# STM32F103ZET6.net
KiCad netlist of a schematic drawn in Altium Designer
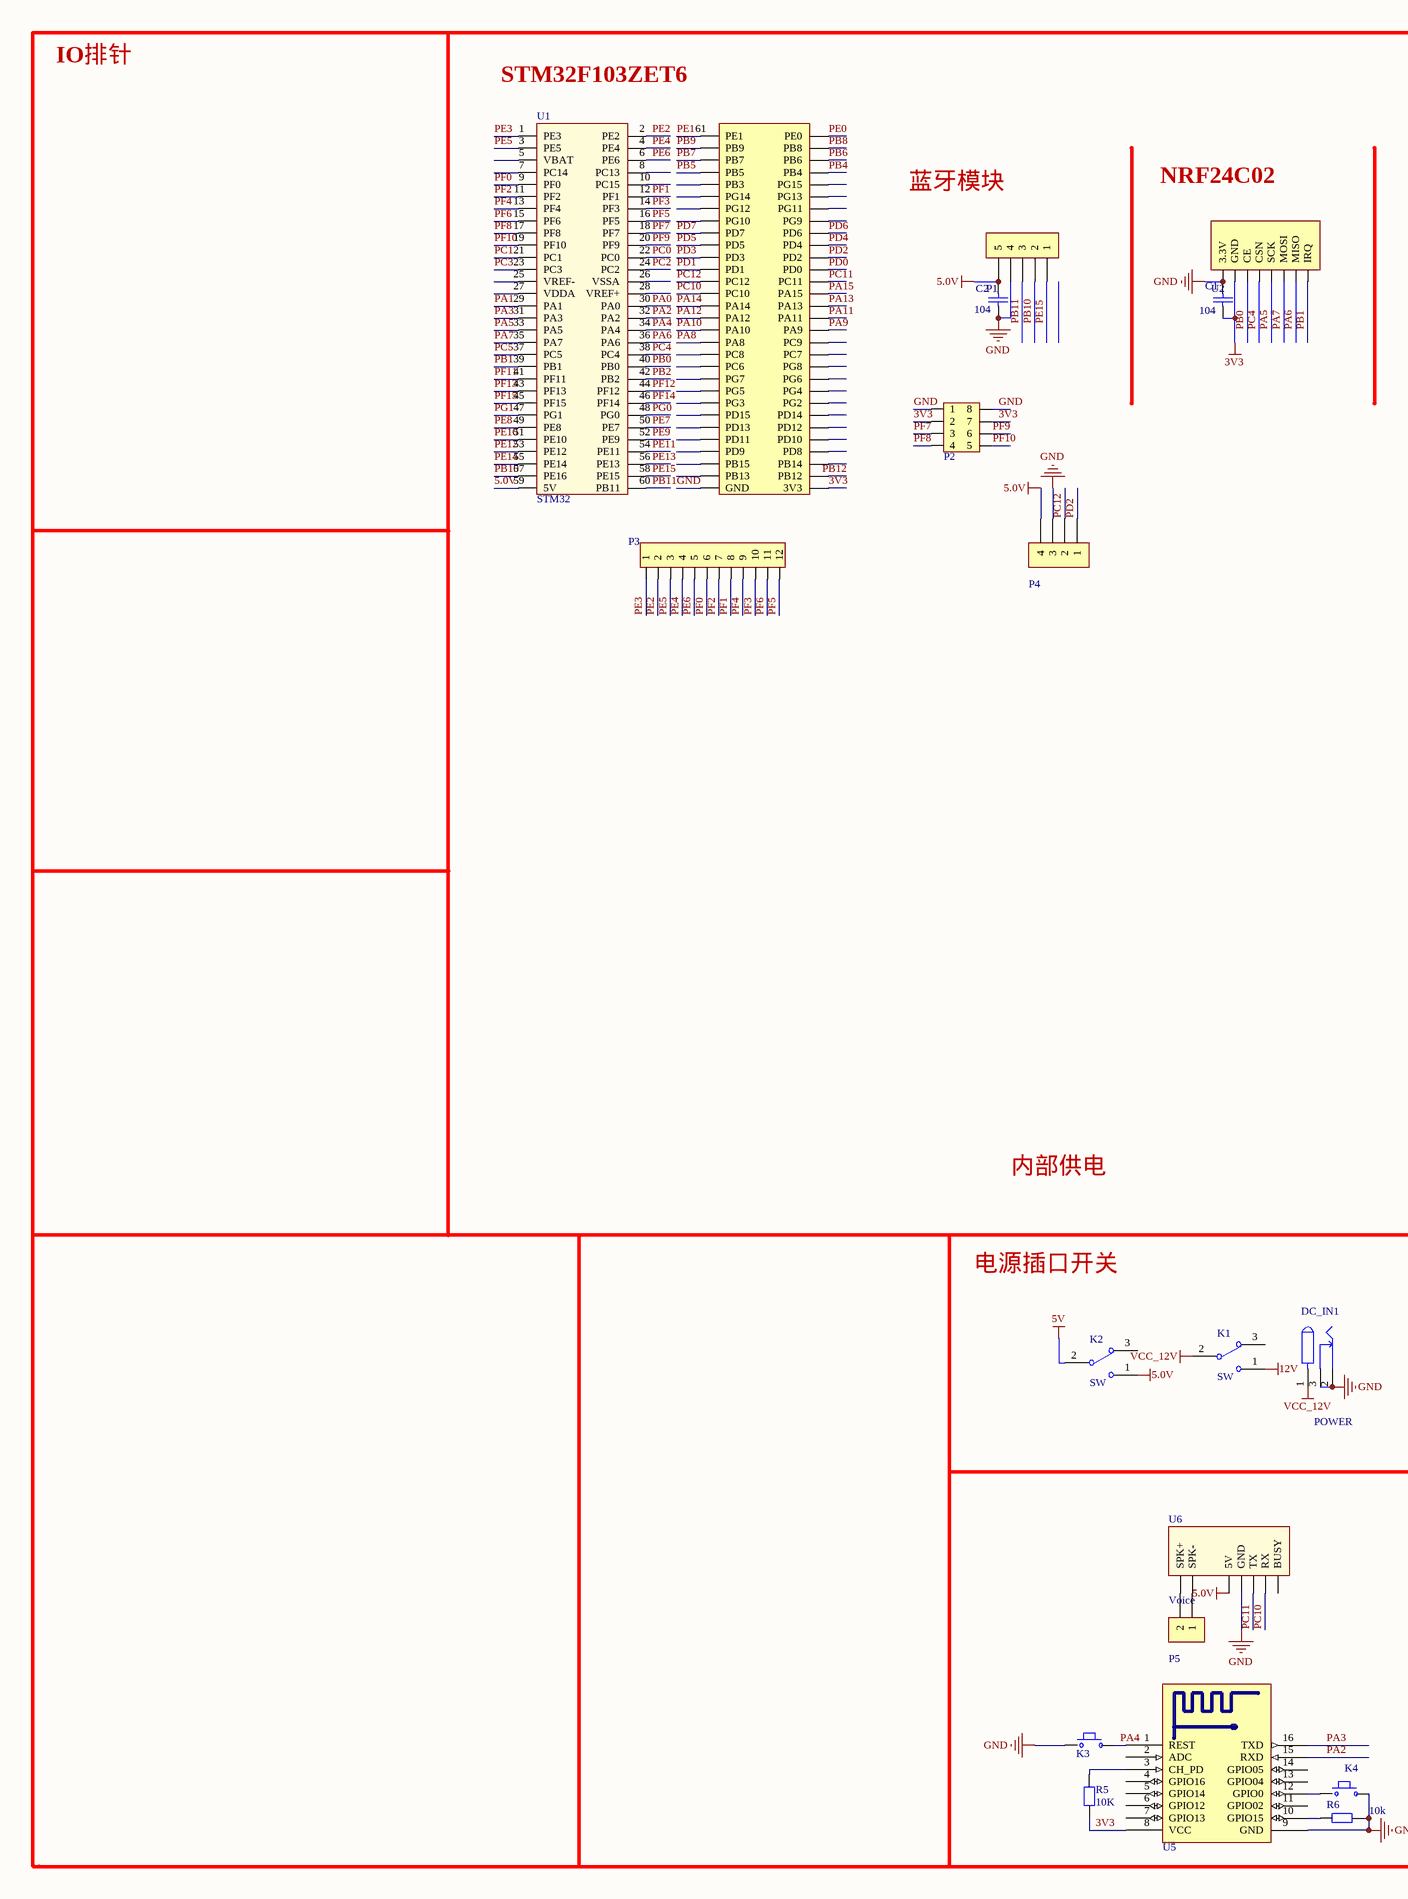
[diagram p0: 原子战舰STM32F103ZET6.SchDoc, left]
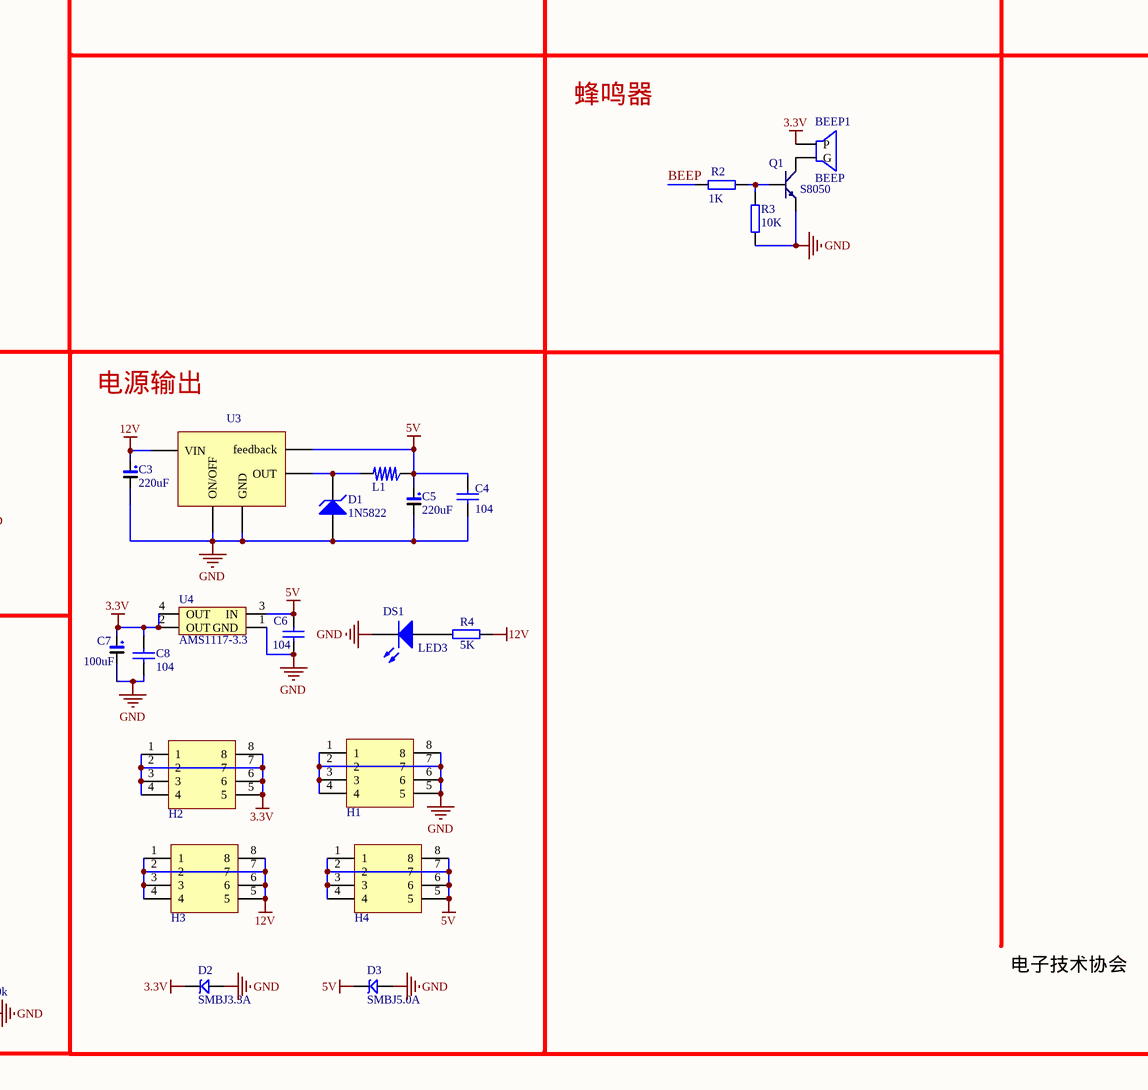
[diagram p1: 原子战舰STM32F103ZET6.SchDoc, right]

(export (version "E")
  (design (tool "Eeschema 10.0.6"))
  (components
    (comp (ref "BEEP1")
      (value "BEEP")
      (footprint "BELL-5")
      (libsource (lib "WarShip V3 STM32103封装库") (part "BEEP"))
    )
    (comp (ref "C1") (value "104") (footprint "C0805") (libsource (lib "周杏发的PCB库") (part "CAP0805")))
    (comp (ref "C2") (value "104") (footprint "C0805") (libsource (lib "周杏发的PCB库") (part "CAP0805")))
    (comp (ref "C3") (value "220uF") (footprint "CAP-470-16V") (libsource (lib "集成库") (part "CAP-470-16V")))
    (comp (ref "C4") (value "104") (footprint "C0805") (libsource (lib "周杏发的PCB库") (part "CAP0805")))
    (comp (ref "C5") (value "220uF") (footprint "CAP-470-16V") (libsource (lib "集成库") (part "CAP-470-16V")))
    (comp (ref "C6") (value "104") (footprint "C0805") (libsource (lib "周杏发的PCB库") (part "CAP0805")))
    (comp (ref "C7") (value "100uF") (footprint "CAP-470-16V") (libsource (lib "集成库") (part "CAP-470-16V")))
    (comp (ref "C8") (value "104") (footprint "C0805") (libsource (lib "周杏发的PCB库") (part "CAP0805")))
    (comp (ref "D1")
      (value "1N5822")
      (footprint "D-9.9X6.0MM")
      (description "Zener Diode")
      (libsource (lib "Miscellaneous Devices") (part "D Zener"))
    )
    (comp (ref "D2")
      (value "SMBJ3.3A")
      (footprint "SMBJ")
      (description "TVS")
      (libsource (lib "WarShip V3 STM32103封装库") (part "SMBJ"))
    )
    (comp (ref "D3")
      (value "SMBJ5.0A")
      (footprint "SMBJ")
      (description "TVS")
      (libsource (lib "WarShip V3 STM32103封装库") (part "SMBJ"))
    )
    (comp (ref "DC_IN1")
      (value "POWER")
      (footprint "DC10B")
      (libsource (lib "WarShip V3 STM32103封装库") (part "POW"))
    )
    (comp (ref "DS1")
      (value "LED3")
      (footprint "SMDLED")
      (description "Typical RED, GREEN, YELLOW, AMBER GaAs LED")
      (fields (field (name "PUBLISHER") "Altium Limited"))
      (libsource (lib "WarShip V3 STM32103封装库") (part "LED2"))
    )
    (comp (ref "H1")
      (value "Header2-4")
      (footprint "Header2-4")
      (libsource (lib "直插原理图库") (part "Header2-4"))
    )
    (comp (ref "H2")
      (value "Header2-4")
      (footprint "Header2-4")
      (libsource (lib "直插原理图库") (part "Header2-4"))
    )
    (comp (ref "H3")
      (value "Header2-4")
      (footprint "Header2-4")
      (libsource (lib "直插原理图库") (part "Header2-4"))
    )
    (comp (ref "H4")
      (value "Header2-4")
      (footprint "Header2-4")
      (libsource (lib "直插原理图库") (part "Header2-4"))
    )
    (comp (ref "K1") (value "SW") (footprint "SW-07") (libsource (lib "PCB_Project1") (part "SW-07")))
    (comp (ref "K2") (value "SW") (footprint "SW-07") (libsource (lib "PCB_Project1") (part "SW-07")))
    (comp (ref "K3") (value "SW-TP") (footprint "SW-TP") (libsource (lib "集成库") (part "SW-TP")))
    (comp (ref "K4") (value "SW-TP") (footprint "SW-TP") (libsource (lib "集成库") (part "SW-TP")))
    (comp (ref "L1")
      (value "4.7uH")
      (footprint "L_SOP74")
      (libsource (lib "WarShip V3 STM32103封装库") (part "L_SOP"))
    )
    (comp (ref "P1") (value "Header5") (footprint "Header5") (libsource (lib "集成库") (part "Header5")))
    (comp (ref "P2") (value "Header4X2") (footprint "Header4X2") (libsource (lib "集成库") (part "Header4X2")))
    (comp (ref "P3") (value "Header12") (footprint "Header12") (libsource (lib "集成库") (part "Header12")))
    (comp (ref "P4") (value "Header4") (footprint "Header4") (libsource (lib "集成库") (part "Header4")))
    (comp (ref "P5") (value "Header2") (footprint "Header2") (libsource (lib "集成库") (part "Header2")))
    (comp (ref "Q1")
      (value "S8050")
      (footprint "SOT-23R")
      (description "8050/BCW846/BCW847")
      (libsource (lib "WarShip V3 STM32103封装库") (part "NPN"))
    )
    (comp (ref "R2") (value "1K") (footprint "R0805") (libsource (lib "周杏发的PCB库") (part "Res-0805")))
    (comp (ref "R3") (value "10K") (footprint "R0805") (libsource (lib "周杏发的PCB库") (part "Res-0805")))
    (comp (ref "R4") (value "5K") (footprint "R0805") (libsource (lib "周杏发的PCB库") (part "Res-0805")))
    (comp (ref "R5") (value "10K") (footprint "RES0805") (libsource (lib "集成库") (part "RES0805")))
    (comp (ref "R6") (value "10k") (footprint "RES0805") (libsource (lib "集成库") (part "RES0805")))
    (comp (ref "U1") (value "STM32") (footprint "STM32") (libsource (lib "集成库") (part "STM32")))
    (comp (ref "U2")
      (value "Mini_24L01")
      (footprint "MINI_24L01")
      (libsource (lib "集成库") (part "Mini_24L01"))
    )
    (comp (ref "U3") (value "LM2596") (footprint "LM2596") (libsource (lib "周杏发的PCB库") (part "LM2596")))
    (comp (ref "U4")
      (value "AMS1117-3.3")
      (footprint "AMS1117")
      (libsource (lib "WarShip V3 STM32103封装库") (part "AMS1117"))
    )
    (comp (ref "U5") (value "ESP-12") (footprint "ESP12") (libsource (lib "esp12") (part "ESP-12")))
    (comp (ref "U6") (value "Voice") (footprint "Voice") (libsource (lib "集成库") (part "Voice")))
  )
  (nets
    (net (code "1") (name "/BEEP") (class "Default")
      (node (ref "R2") (pin "1") (pinfunction "1_1") (pintype "passive"))
    )
    (net (code "2") (name "/PA0") (class "Default")
      (node (ref "U1") (pin "30") (pinfunction "PA0_30") (pintype "passive"))
    )
    (net (code "3") (name "/PA1") (class "Default")
      (node (ref "U1") (pin "29") (pinfunction "PA1_29") (pintype "passive"))
    )
    (net (code "4") (name "/PA2") (class "Default")
      (node (ref "U1") (pin "32") (pinfunction "PA2_32") (pintype "passive"))
      (node (ref "U5") (pin "15") (pinfunction "RXD_15") (pintype "input"))
    )
    (net (code "5") (name "/PA3") (class "Default")
      (node (ref "U1") (pin "31") (pinfunction "PA3_31") (pintype "passive"))
      (node (ref "U5") (pin "16") (pinfunction "TXD_16") (pintype "output"))
    )
    (net (code "6") (name "/PA4") (class "Default")
      (node (ref "K3") (pin "2") (pinfunction "2_2") (pintype "passive"))
      (node (ref "U1") (pin "34") (pinfunction "PA4_34") (pintype "passive"))
      (node (ref "U5") (pin "1") (pinfunction "REST_1") (pintype "passive"))
    )
    (net (code "7") (name "/PA5") (class "Default")
      (node (ref "U1") (pin "33") (pinfunction "PA5_33") (pintype "passive"))
      (node (ref "U2") (pin "5") (pinfunction "SCK_5") (pintype "passive"))
    )
    (net (code "8") (name "/PA6") (class "Default")
      (node (ref "U1") (pin "36") (pinfunction "PA6_36") (pintype "passive"))
      (node (ref "U2") (pin "7") (pinfunction "MISO_7") (pintype "passive"))
    )
    (net (code "9") (name "/PA7") (class "Default")
      (node (ref "U1") (pin "35") (pinfunction "PA7_35") (pintype "passive"))
      (node (ref "U2") (pin "6") (pinfunction "MOSI_6") (pintype "passive"))
    )
    (net (code "10") (name "/PA8") (class "Default")
      (node (ref "U1") (pin "78") (pinfunction "PA8_78") (pintype "passive"))
    )
    (net (code "11") (name "/PA9") (class "Default")
      (node (ref "U1") (pin "104") (pinfunction "PA9_104") (pintype "passive"))
    )
    (net (code "12") (name "/PA10") (class "Default")
      (node (ref "U1") (pin "77") (pinfunction "PA10_77") (pintype "passive"))
    )
    (net (code "13") (name "/PA11") (class "Default")
      (node (ref "U1") (pin "105") (pinfunction "PA11_105") (pintype "passive"))
    )
    (net (code "14") (name "/PA12") (class "Default")
      (node (ref "U1") (pin "76") (pinfunction "PA12_76") (pintype "passive"))
    )
    (net (code "15") (name "/PA13") (class "Default")
      (node (ref "U1") (pin "106") (pinfunction "PA13_106") (pintype "passive"))
    )
    (net (code "16") (name "/PA14") (class "Default")
      (node (ref "U1") (pin "75") (pinfunction "PA14_75") (pintype "passive"))
    )
    (net (code "17") (name "/PA15") (class "Default")
      (node (ref "U1") (pin "107") (pinfunction "PA15_107") (pintype "passive"))
    )
    (net (code "18") (name "/PB0") (class "Default")
      (node (ref "U1") (pin "40") (pinfunction "PB0_40") (pintype "passive"))
      (node (ref "U2") (pin "3") (pinfunction "CE_3") (pintype "passive"))
    )
    (net (code "19") (name "/PB1") (class "Default")
      (node (ref "U1") (pin "39") (pinfunction "PB1_39") (pintype "passive"))
      (node (ref "U2") (pin "8") (pinfunction "IRQ_8") (pintype "passive"))
    )
    (net (code "20") (name "/PB2") (class "Default")
      (node (ref "U1") (pin "42") (pinfunction "PB2_42") (pintype "passive"))
    )
    (net (code "21") (name "/PB4") (class "Default")
      (node (ref "U1") (pin "117") (pinfunction "PB4_117") (pintype "passive"))
    )
    (net (code "22") (name "/PB5") (class "Default")
      (node (ref "U1") (pin "64") (pinfunction "PB5_64") (pintype "passive"))
    )
    (net (code "23") (name "/PB6") (class "Default")
      (node (ref "U1") (pin "118") (pinfunction "PB6_118") (pintype "passive"))
    )
    (net (code "24") (name "/PB7") (class "Default")
      (node (ref "U1") (pin "63") (pinfunction "PB7_63") (pintype "passive"))
    )
    (net (code "25") (name "/PB8") (class "Default")
      (node (ref "U1") (pin "119") (pinfunction "PB8_119") (pintype "passive"))
    )
    (net (code "26") (name "/PB9") (class "Default")
      (node (ref "U1") (pin "62") (pinfunction "PB9_62") (pintype "passive"))
    )
    (net (code "27") (name "/PB10") (class "Default")
      (node (ref "P1") (pin "2") (pinfunction "2_2") (pintype "passive"))
      (node (ref "U1") (pin "57") (pinfunction "PE16_57") (pintype "passive"))
    )
    (net (code "28") (name "/PB11") (class "Default")
      (node (ref "P1") (pin "3") (pinfunction "3_3") (pintype "passive"))
      (node (ref "U1") (pin "60") (pinfunction "PB11_60") (pintype "passive"))
    )
    (net (code "30") (name "/PC0") (class "Default")
      (node (ref "U1") (pin "22") (pinfunction "PC0_22") (pintype "passive"))
    )
    (net (code "31") (name "/PC1") (class "Default")
      (node (ref "U1") (pin "21") (pinfunction "PC1_21") (pintype "passive"))
    )
    (net (code "32") (name "/PC2") (class "Default")
      (node (ref "U1") (pin "24") (pinfunction "PC2_24") (pintype "passive"))
    )
    (net (code "33") (name "/PC3") (class "Default")
      (node (ref "U1") (pin "23") (pinfunction "PC3_23") (pintype "passive"))
    )
    (net (code "34") (name "/PC4") (class "Default")
      (node (ref "U1") (pin "38") (pinfunction "PC4_38") (pintype "passive"))
      (node (ref "U2") (pin "4") (pinfunction "CSN_4") (pintype "passive"))
    )
    (net (code "35") (name "/PC5") (class "Default")
      (node (ref "U1") (pin "37") (pinfunction "PC5_37") (pintype "passive"))
    )
    (net (code "36") (name "/PC10") (class "Default")
      (node (ref "U1") (pin "74") (pinfunction "PC10_74") (pintype "passive"))
      (node (ref "U6") (pin "5") (pinfunction "RX_5") (pintype "passive"))
    )
    (net (code "37") (name "/PC11") (class "Default")
      (node (ref "U1") (pin "108") (pinfunction "PC11_108") (pintype "passive"))
      (node (ref "U6") (pin "4") (pinfunction "TX_4") (pintype "passive"))
    )
    (net (code "38") (name "/PC12") (class "Default")
      (node (ref "P4") (pin "2") (pinfunction "2_2") (pintype "passive"))
      (node (ref "U1") (pin "73") (pinfunction "PC12_73") (pintype "passive"))
    )
    (net (code "39") (name "/PD0") (class "Default")
      (node (ref "U1") (pin "109") (pinfunction "PD0_109") (pintype "passive"))
    )
    (net (code "40") (name "/PD1") (class "Default")
      (node (ref "U1") (pin "72") (pinfunction "PD1_72") (pintype "passive"))
    )
    (net (code "41") (name "/PD2") (class "Default")
      (node (ref "P4") (pin "1") (pinfunction "1_1") (pintype "passive"))
      (node (ref "U1") (pin "110") (pinfunction "PD2_110") (pintype "passive"))
    )
    (net (code "42") (name "/PD3") (class "Default")
      (node (ref "U1") (pin "71") (pinfunction "PD3_71") (pintype "passive"))
    )
    (net (code "43") (name "/PD4") (class "Default")
      (node (ref "U1") (pin "111") (pinfunction "PD4_111") (pintype "passive"))
    )
    (net (code "44") (name "/PD5") (class "Default")
      (node (ref "U1") (pin "70") (pinfunction "PD5_70") (pintype "passive"))
    )
    (net (code "45") (name "/PD6") (class "Default")
      (node (ref "U1") (pin "112") (pinfunction "PD6_112") (pintype "passive"))
    )
    (net (code "46") (name "/PD7") (class "Default")
      (node (ref "U1") (pin "69") (pinfunction "PD7_69") (pintype "passive"))
    )
    (net (code "47") (name "/PE0") (class "Default")
      (node (ref "U1") (pin "120") (pinfunction "PE0_120") (pintype "passive"))
    )
    (net (code "48") (name "/PE1") (class "Default")
      (node (ref "U1") (pin "61") (pinfunction "PE1_61") (pintype "passive"))
    )
    (net (code "49") (name "/PE2") (class "Default")
      (node (ref "P3") (pin "2") (pinfunction "2_2") (pintype "passive"))
      (node (ref "U1") (pin "2") (pinfunction "PE2_2") (pintype "passive"))
    )
    (net (code "50") (name "/PE3") (class "Default")
      (node (ref "P3") (pin "1") (pinfunction "1_1") (pintype "passive"))
      (node (ref "U1") (pin "1") (pinfunction "PE3_1") (pintype "passive"))
    )
    (net (code "51") (name "/PE4") (class "Default")
      (node (ref "P3") (pin "4") (pinfunction "4_4") (pintype "passive"))
      (node (ref "U1") (pin "4") (pinfunction "PE4_4") (pintype "passive"))
    )
    (net (code "52") (name "/PE5") (class "Default")
      (node (ref "P3") (pin "3") (pinfunction "3_3") (pintype "passive"))
      (node (ref "U1") (pin "3") (pinfunction "PE5_3") (pintype "passive"))
    )
    (net (code "53") (name "/PE6") (class "Default")
      (node (ref "P3") (pin "5") (pinfunction "5_5") (pintype "passive"))
      (node (ref "U1") (pin "6") (pinfunction "PE6_6") (pintype "passive"))
    )
    (net (code "54") (name "/PE7") (class "Default")
      (node (ref "U1") (pin "50") (pinfunction "PE7_50") (pintype "passive"))
    )
    (net (code "55") (name "/PE8") (class "Default")
      (node (ref "U1") (pin "49") (pinfunction "PE8_49") (pintype "passive"))
    )
    (net (code "56") (name "/PE9") (class "Default")
      (node (ref "U1") (pin "52") (pinfunction "PE9_52") (pintype "passive"))
    )
    (net (code "57") (name "/PE10") (class "Default")
      (node (ref "U1") (pin "51") (pinfunction "PE10_51") (pintype "passive"))
    )
    (net (code "58") (name "/PE11") (class "Default")
      (node (ref "U1") (pin "54") (pinfunction "PE11_54") (pintype "passive"))
    )
    (net (code "59") (name "/PE12") (class "Default")
      (node (ref "U1") (pin "53") (pinfunction "PE12_53") (pintype "passive"))
    )
    (net (code "60") (name "/PE13") (class "Default")
      (node (ref "U1") (pin "56") (pinfunction "PE13_56") (pintype "passive"))
    )
    (net (code "61") (name "/PE14") (class "Default")
      (node (ref "U1") (pin "55") (pinfunction "PE14_55") (pintype "passive"))
    )
    (net (code "62") (name "/PE15") (class "Default")
      (node (ref "P1") (pin "1") (pinfunction "1_1") (pintype "passive"))
      (node (ref "U1") (pin "58") (pinfunction "PE15_58") (pintype "passive"))
    )
    (net (code "63") (name "/PF0") (class "Default")
      (node (ref "P3") (pin "6") (pinfunction "6_6") (pintype "passive"))
      (node (ref "U1") (pin "9") (pinfunction "PF0_9") (pintype "passive"))
    )
    (net (code "64") (name "/PF1") (class "Default")
      (node (ref "P3") (pin "8") (pinfunction "8_8") (pintype "passive"))
      (node (ref "U1") (pin "12") (pinfunction "PF1_12") (pintype "passive"))
    )
    (net (code "65") (name "/PF2") (class "Default")
      (node (ref "P3") (pin "7") (pinfunction "7_7") (pintype "passive"))
      (node (ref "U1") (pin "11") (pinfunction "PF2_11") (pintype "passive"))
    )
    (net (code "66") (name "/PF3") (class "Default")
      (node (ref "P3") (pin "10") (pinfunction "10_10") (pintype "passive"))
      (node (ref "U1") (pin "14") (pinfunction "PF3_14") (pintype "passive"))
    )
    (net (code "67") (name "/PF4") (class "Default")
      (node (ref "P3") (pin "9") (pinfunction "9_9") (pintype "passive"))
      (node (ref "U1") (pin "13") (pinfunction "PF4_13") (pintype "passive"))
    )
    (net (code "68") (name "/PF5") (class "Default")
      (node (ref "P3") (pin "12") (pinfunction "12_12") (pintype "passive"))
      (node (ref "U1") (pin "16") (pinfunction "PF5_16") (pintype "passive"))
    )
    (net (code "69") (name "/PF6") (class "Default")
      (node (ref "P3") (pin "11") (pinfunction "11_11") (pintype "passive"))
      (node (ref "U1") (pin "15") (pinfunction "PF6_15") (pintype "passive"))
    )
    (net (code "70") (name "/PF7") (class "Default")
      (node (ref "P2") (pin "3") (pinfunction "3_3") (pintype "passive"))
      (node (ref "U1") (pin "18") (pinfunction "PF7_18") (pintype "passive"))
    )
    (net (code "71") (name "/PF8") (class "Default")
      (node (ref "P2") (pin "4") (pinfunction "4_4") (pintype "passive"))
      (node (ref "U1") (pin "17") (pinfunction "PF8_17") (pintype "passive"))
    )
    (net (code "72") (name "/PF9") (class "Default")
      (node (ref "P2") (pin "6") (pinfunction "6_6") (pintype "passive"))
      (node (ref "U1") (pin "20") (pinfunction "PF9_20") (pintype "passive"))
    )
    (net (code "73") (name "/PF10") (class "Default")
      (node (ref "P2") (pin "5") (pinfunction "5_5") (pintype "passive"))
      (node (ref "U1") (pin "19") (pinfunction "PF10_19") (pintype "passive"))
    )
    (net (code "74") (name "/PF11") (class "Default")
      (node (ref "U1") (pin "41") (pinfunction "PF11_41") (pintype "passive"))
    )
    (net (code "75") (name "/PF12") (class "Default")
      (node (ref "U1") (pin "44") (pinfunction "PF12_44") (pintype "passive"))
    )
    (net (code "76") (name "/PF13") (class "Default")
      (node (ref "U1") (pin "43") (pinfunction "PF13_43") (pintype "passive"))
    )
    (net (code "77") (name "/PF14") (class "Default")
      (node (ref "U1") (pin "46") (pinfunction "PF14_46") (pintype "passive"))
    )
    (net (code "78") (name "/PF15") (class "Default")
      (node (ref "U1") (pin "45") (pinfunction "PF15_45") (pintype "passive"))
    )
    (net (code "79") (name "/PG0") (class "Default")
      (node (ref "U1") (pin "48") (pinfunction "PG0_48") (pintype "passive"))
    )
    (net (code "80") (name "/PG1") (class "Default")
      (node (ref "U1") (pin "47") (pinfunction "PG1_47") (pintype "passive"))
    )
    (net (code "82") (name "3.3V") (class "Default")
      (node (ref "BEEP1") (pin "1") (pinfunction "P_1") (pintype "passive"))
      (node (ref "C7") (pin "1") (pinfunction "1_1") (pintype "passive"))
      (node (ref "C8") (pin "2") (pinfunction "2_2") (pintype "passive"))
      (node (ref "D2") (pin "2") (pintype "passive"))
      (node (ref "H2") (pin "1") (pinfunction "1_1") (pintype "passive"))
      (node (ref "H2") (pin "2") (pinfunction "2_2") (pintype "passive"))
      (node (ref "H2") (pin "3") (pinfunction "3_3") (pintype "passive"))
      (node (ref "H2") (pin "4") (pinfunction "4_4") (pintype "passive"))
      (node (ref "H2") (pin "5") (pinfunction "5_5") (pintype "passive"))
      (node (ref "H2") (pin "6") (pinfunction "6_6") (pintype "passive"))
      (node (ref "H2") (pin "7") (pinfunction "7_7") (pintype "passive"))
      (node (ref "H2") (pin "8") (pinfunction "8_8") (pintype "passive"))
      (node (ref "U4") (pin "2") (pinfunction "OUT_2") (pintype "passive"))
      (node (ref "U4") (pin "4") (pinfunction "OUT_4") (pintype "passive"))
    )
    (net (code "83") (name "3V3") (class "Default")
      (node (ref "C1") (pin "1") (pinfunction "1_1") (pintype "passive"))
      (node (ref "P2") (pin "2") (pinfunction "2_2") (pintype "passive"))
      (node (ref "P2") (pin "7") (pinfunction "7_7") (pintype "passive"))
      (node (ref "R5") (pin "1") (pinfunction "1_1") (pintype "passive"))
      (node (ref "U1") (pin "91") (pinfunction "3V3_91") (pintype "passive"))
      (node (ref "U2") (pin "2") (pinfunction "GND_2") (pintype "passive"))
      (node (ref "U5") (pin "8") (pinfunction "VCC_8") (pintype "power_in"))
    )
    (net (code "84") (name "5.0V") (class "Default")
      (node (ref "C2") (pin "2") (pinfunction "2_2") (pintype "passive"))
      (node (ref "K2") (pin "1") (pinfunction "1_1") (pintype "passive"))
      (node (ref "P1") (pin "5") (pinfunction "5_5") (pintype "passive"))
      (node (ref "P4") (pin "4") (pinfunction "4_4") (pintype "passive"))
      (node (ref "U1") (pin "59") (pinfunction "5V_59") (pintype "passive"))
      (node (ref "U6") (pin "2") (pinfunction "5V_2") (pintype "passive"))
    )
    (net (code "85") (name "5V") (class "Default")
      (node (ref "C4") (pin "2") (pinfunction "2_2") (pintype "passive"))
      (node (ref "C5") (pin "1") (pinfunction "1_1") (pintype "passive"))
      (node (ref "C6") (pin "2") (pinfunction "2_2") (pintype "passive"))
      (node (ref "D3") (pin "2") (pintype "passive"))
      (node (ref "H4") (pin "1") (pinfunction "1_1") (pintype "passive"))
      (node (ref "H4") (pin "2") (pinfunction "2_2") (pintype "passive"))
      (node (ref "H4") (pin "3") (pinfunction "3_3") (pintype "passive"))
      (node (ref "H4") (pin "4") (pinfunction "4_4") (pintype "passive"))
      (node (ref "H4") (pin "5") (pinfunction "5_5") (pintype "passive"))
      (node (ref "H4") (pin "6") (pinfunction "6_6") (pintype "passive"))
      (node (ref "H4") (pin "7") (pinfunction "7_7") (pintype "passive"))
      (node (ref "H4") (pin "8") (pinfunction "8_8") (pintype "passive"))
      (node (ref "K2") (pin "2") (pinfunction "2_2") (pintype "passive"))
      (node (ref "L1") (pin "1") (pinfunction "1_1") (pintype "passive"))
      (node (ref "U3") (pin "4") (pinfunction "feedback_4") (pintype "passive"))
      (node (ref "U4") (pin "3") (pinfunction "IN_3") (pintype "passive"))
    )
    (net (code "86") (name "12V") (class "Default")
      (node (ref "C3") (pin "1") (pinfunction "1_1") (pintype "passive"))
      (node (ref "H3") (pin "1") (pinfunction "1_1") (pintype "passive"))
      (node (ref "H3") (pin "2") (pinfunction "2_2") (pintype "passive"))
      (node (ref "H3") (pin "3") (pinfunction "3_3") (pintype "passive"))
      (node (ref "H3") (pin "4") (pinfunction "4_4") (pintype "passive"))
      (node (ref "H3") (pin "5") (pinfunction "5_5") (pintype "passive"))
      (node (ref "H3") (pin "6") (pinfunction "6_6") (pintype "passive"))
      (node (ref "H3") (pin "7") (pinfunction "7_7") (pintype "passive"))
      (node (ref "H3") (pin "8") (pinfunction "8_8") (pintype "passive"))
      (node (ref "K1") (pin "1") (pinfunction "1_1") (pintype "passive"))
      (node (ref "R4") (pin "2") (pinfunction "2_2") (pintype "passive"))
      (node (ref "U3") (pin "1") (pinfunction "VIN_1") (pintype "passive"))
    )
    (net (code "87") (name "GND") (class "Default")
      (node (ref "C1") (pin "2") (pinfunction "2_2") (pintype "passive"))
      (node (ref "C2") (pin "1") (pinfunction "1_1") (pintype "passive"))
      (node (ref "C3") (pin "2") (pinfunction "2_2") (pintype "passive"))
      (node (ref "C4") (pin "1") (pinfunction "1_1") (pintype "passive"))
      (node (ref "C5") (pin "2") (pinfunction "2_2") (pintype "passive"))
      (node (ref "C6") (pin "1") (pinfunction "1_1") (pintype "passive"))
      (node (ref "C7") (pin "2") (pinfunction "2_2") (pintype "passive"))
      (node (ref "C8") (pin "1") (pinfunction "1_1") (pintype "passive"))
      (node (ref "D1") (pin "1") (pinfunction "A_1") (pintype "passive"))
      (node (ref "D2") (pin "1") (pintype "passive"))
      (node (ref "D3") (pin "1") (pintype "passive"))
      (node (ref "DC_IN1") (pin "2") (pintype "passive"))
      (node (ref "DC_IN1") (pin "3") (pintype "passive"))
      (node (ref "DS1") (pin "2") (pinfunction "K_2") (pintype "passive"))
      (node (ref "H1") (pin "1") (pinfunction "1_1") (pintype "passive"))
      (node (ref "H1") (pin "2") (pinfunction "2_2") (pintype "passive"))
      (node (ref "H1") (pin "3") (pinfunction "3_3") (pintype "passive"))
      (node (ref "H1") (pin "4") (pinfunction "4_4") (pintype "passive"))
      (node (ref "H1") (pin "5") (pinfunction "5_5") (pintype "passive"))
      (node (ref "H1") (pin "6") (pinfunction "6_6") (pintype "passive"))
      (node (ref "H1") (pin "7") (pinfunction "7_7") (pintype "passive"))
      (node (ref "H1") (pin "8") (pinfunction "8_8") (pintype "passive"))
      (node (ref "K3") (pin "1") (pinfunction "1_1") (pintype "passive"))
      (node (ref "K4") (pin "2") (pinfunction "2_2") (pintype "passive"))
      (node (ref "P1") (pin "4") (pinfunction "4_4") (pintype "passive"))
      (node (ref "P2") (pin "1") (pinfunction "1_1") (pintype "passive"))
      (node (ref "P2") (pin "8") (pinfunction "8_8") (pintype "passive"))
      (node (ref "P4") (pin "3") (pinfunction "3_3") (pintype "passive"))
      (node (ref "Q1") (pin "1") (pinfunction "E_1") (pintype "passive"))
      (node (ref "R3") (pin "1") (pinfunction "1_1") (pintype "passive"))
      (node (ref "R6") (pin "2") (pinfunction "2_2") (pintype "passive"))
      (node (ref "U1") (pin "90") (pinfunction "GND_90") (pintype "passive"))
      (node (ref "U2") (pin "1") (pinfunction "3.3V_1") (pintype "passive"))
      (node (ref "U3") (pin "3") (pinfunction "GND_3") (pintype "passive"))
      (node (ref "U3") (pin "5") (pinfunction "ON/OFF_5") (pintype "passive"))
      (node (ref "U4") (pin "1") (pinfunction "GND_1") (pintype "passive"))
      (node (ref "U5") (pin "9") (pinfunction "GND_9") (pintype "power_in"))
      (node (ref "U6") (pin "3") (pinfunction "GND_3") (pintype "passive"))
    )
    (net (code "88") (name "Net-(BEEP1-G)") (class "Default")
      (node (ref "BEEP1") (pin "2") (pinfunction "G_2") (pintype "passive"))
      (node (ref "Q1") (pin "3") (pinfunction "C_3") (pintype "passive"))
    )
    (net (code "89") (name "Net-(D1-K)") (class "Default")
      (node (ref "D1") (pin "2") (pinfunction "K_2") (pintype "passive"))
      (node (ref "L1") (pin "2") (pinfunction "2_2") (pintype "passive"))
      (node (ref "U3") (pin "2") (pinfunction "OUT_2") (pintype "passive"))
    )
    (net (code "90") (name "Net-(DS1-A)") (class "Default")
      (node (ref "DS1") (pin "1") (pinfunction "A_1") (pintype "passive"))
      (node (ref "R4") (pin "1") (pinfunction "1_1") (pintype "passive"))
    )
    (net (code "91") (name "Net-(Q1-B)") (class "Default")
      (node (ref "Q1") (pin "2") (pinfunction "B_2") (pintype "passive"))
      (node (ref "R2") (pin "2") (pinfunction "2_2") (pintype "passive"))
      (node (ref "R3") (pin "2") (pinfunction "2_2") (pintype "passive"))
    )
    (net (code "92") (name "Net-(U5-CH_PD)") (class "Default")
      (node (ref "R5") (pin "2") (pinfunction "2_2") (pintype "passive"))
      (node (ref "U5") (pin "3") (pinfunction "CH_PD_3") (pintype "input"))
    )
    (net (code "93") (name "Net-(U5-GPIO0)") (class "Default")
      (node (ref "K4") (pin "1") (pinfunction "1_1") (pintype "passive"))
      (node (ref "U5") (pin "12") (pinfunction "GPIO0_12") (pintype "bidirectional"))
    )
    (net (code "94") (name "Net-(U5-GPIO15)") (class "Default")
      (node (ref "R6") (pin "1") (pinfunction "1_1") (pintype "passive"))
      (node (ref "U5") (pin "10") (pinfunction "GPIO15_10") (pintype "bidirectional"))
    )
    (net (code "95") (name "Net-(U6-SPK+)") (class "Default")
      (node (ref "P5") (pin "2") (pinfunction "2_2") (pintype "passive"))
      (node (ref "U6") (pin "0") (pinfunction "SPK+_0") (pintype "passive"))
    )
    (net (code "96") (name "Net-(U6-SPK-)") (class "Default")
      (node (ref "P5") (pin "1") (pinfunction "1_1") (pintype "passive"))
      (node (ref "U6") (pin "1") (pinfunction "SPK-_1") (pintype "passive"))
    )
    (net (code "97") (name "VCC_12V") (class "Default")
      (node (ref "DC_IN1") (pin "1") (pintype "passive"))
      (node (ref "K1") (pin "2") (pinfunction "2_2") (pintype "passive"))
    )
    (net (code "98") (name "unconnected-(K1-Pad3)") (class "Default")
      (node (ref "K1") (pin "3") (pinfunction "3_3") (pintype "passive"))
    )
    (net (code "99") (name "unconnected-(K2-Pad3)") (class "Default")
      (node (ref "K2") (pin "3") (pinfunction "3_3") (pintype "passive"))
    )
    (net (code "100") (name "unconnected-(U1-PB3-Pad65)") (class "Default")
      (node (ref "U1") (pin "65") (pinfunction "PB3_65") (pintype "passive"))
    )
    (net (code "101") (name "unconnected-(U1-PB12-Pad92)") (class "Default")
      (node (ref "U1") (pin "92") (pinfunction "PB12_92") (pintype "passive"))
    )
    (net (code "102") (name "unconnected-(U1-PB13-Pad89)") (class "Default")
      (node (ref "U1") (pin "89") (pinfunction "PB13_89") (pintype "passive"))
    )
    (net (code "103") (name "unconnected-(U1-PB14-Pad93)") (class "Default")
      (node (ref "U1") (pin "93") (pinfunction "PB14_93") (pintype "passive"))
    )
    (net (code "104") (name "unconnected-(U1-PB15-Pad88)") (class "Default")
      (node (ref "U1") (pin "88") (pinfunction "PB15_88") (pintype "passive"))
    )
    (net (code "105") (name "unconnected-(U1-PC6-Pad80)") (class "Default")
      (node (ref "U1") (pin "80") (pinfunction "PC6_80") (pintype "passive"))
    )
    (net (code "106") (name "unconnected-(U1-PC7-Pad102)") (class "Default")
      (node (ref "U1") (pin "102") (pinfunction "PC7_102") (pintype "passive"))
    )
    (net (code "107") (name "unconnected-(U1-PC8-Pad79)") (class "Default")
      (node (ref "U1") (pin "79") (pinfunction "PC8_79") (pintype "passive"))
    )
    (net (code "108") (name "unconnected-(U1-PC9-Pad103)") (class "Default")
      (node (ref "U1") (pin "103") (pinfunction "PC9_103") (pintype "passive"))
    )
    (net (code "109") (name "unconnected-(U1-PC13-Pad8)") (class "Default")
      (node (ref "U1") (pin "8") (pinfunction "PC13_8") (pintype "passive"))
    )
    (net (code "110") (name "unconnected-(U1-PC14-Pad7)") (class "Default")
      (node (ref "U1") (pin "7") (pinfunction "PC14_7") (pintype "passive"))
    )
    (net (code "111") (name "unconnected-(U1-PC15-Pad10)") (class "Default")
      (node (ref "U1") (pin "10") (pinfunction "PC15_10") (pintype "passive"))
    )
    (net (code "112") (name "unconnected-(U1-PD8-Pad94)") (class "Default")
      (node (ref "U1") (pin "94") (pinfunction "PD8_94") (pintype "passive"))
    )
    (net (code "113") (name "unconnected-(U1-PD9-Pad87)") (class "Default")
      (node (ref "U1") (pin "87") (pinfunction "PD9_87") (pintype "passive"))
    )
    (net (code "114") (name "unconnected-(U1-PD10-Pad95)") (class "Default")
      (node (ref "U1") (pin "95") (pinfunction "PD10_95") (pintype "passive"))
    )
    (net (code "115") (name "unconnected-(U1-PD11-Pad86)") (class "Default")
      (node (ref "U1") (pin "86") (pinfunction "PD11_86") (pintype "passive"))
    )
    (net (code "116") (name "unconnected-(U1-PD12-Pad96)") (class "Default")
      (node (ref "U1") (pin "96") (pinfunction "PD12_96") (pintype "passive"))
    )
    (net (code "117") (name "unconnected-(U1-PD13-Pad85)") (class "Default")
      (node (ref "U1") (pin "85") (pinfunction "PD13_85") (pintype "passive"))
    )
    (net (code "118") (name "unconnected-(U1-PD14-Pad97)") (class "Default")
      (node (ref "U1") (pin "97") (pinfunction "PD14_97") (pintype "passive"))
    )
    (net (code "119") (name "unconnected-(U1-PD15-Pad84)") (class "Default")
      (node (ref "U1") (pin "84") (pinfunction "PD15_84") (pintype "passive"))
    )
    (net (code "120") (name "unconnected-(U1-PG2-Pad98)") (class "Default")
      (node (ref "U1") (pin "98") (pinfunction "PG2_98") (pintype "passive"))
    )
    (net (code "121") (name "unconnected-(U1-PG3-Pad83)") (class "Default")
      (node (ref "U1") (pin "83") (pinfunction "PG3_83") (pintype "passive"))
    )
    (net (code "122") (name "unconnected-(U1-PG4-Pad99)") (class "Default")
      (node (ref "U1") (pin "99") (pinfunction "PG4_99") (pintype "passive"))
    )
    (net (code "123") (name "unconnected-(U1-PG5-Pad82)") (class "Default")
      (node (ref "U1") (pin "82") (pinfunction "PG5_82") (pintype "passive"))
    )
    (net (code "124") (name "unconnected-(U1-PG6-Pad100)") (class "Default")
      (node (ref "U1") (pin "100") (pinfunction "PG6_100") (pintype "passive"))
    )
    (net (code "125") (name "unconnected-(U1-PG7-Pad81)") (class "Default")
      (node (ref "U1") (pin "81") (pinfunction "PG7_81") (pintype "passive"))
    )
    (net (code "126") (name "unconnected-(U1-PG8-Pad101)") (class "Default")
      (node (ref "U1") (pin "101") (pinfunction "PG8_101") (pintype "passive"))
    )
    (net (code "127") (name "unconnected-(U1-PG9-Pad113)") (class "Default")
      (node (ref "U1") (pin "113") (pinfunction "PG9_113") (pintype "passive"))
    )
    (net (code "128") (name "unconnected-(U1-PG10-Pad68)") (class "Default")
      (node (ref "U1") (pin "68") (pinfunction "PG10_68") (pintype "passive"))
    )
    (net (code "129") (name "unconnected-(U1-PG11-Pad114)") (class "Default")
      (node (ref "U1") (pin "114") (pinfunction "PG11_114") (pintype "passive"))
    )
    (net (code "130") (name "unconnected-(U1-PG12-Pad67)") (class "Default")
      (node (ref "U1") (pin "67") (pinfunction "PG12_67") (pintype "passive"))
    )
    (net (code "131") (name "unconnected-(U1-PG13-Pad115)") (class "Default")
      (node (ref "U1") (pin "115") (pinfunction "PG13_115") (pintype "passive"))
    )
    (net (code "132") (name "unconnected-(U1-PG14-Pad66)") (class "Default")
      (node (ref "U1") (pin "66") (pinfunction "PG14_66") (pintype "passive"))
    )
    (net (code "133") (name "unconnected-(U1-PG15-Pad116)") (class "Default")
      (node (ref "U1") (pin "116") (pinfunction "PG15_116") (pintype "passive"))
    )
    (net (code "134") (name "unconnected-(U1-VBAT-Pad5)") (class "Default")
      (node (ref "U1") (pin "5") (pinfunction "VBAT_5") (pintype "passive"))
    )
    (net (code "135") (name "unconnected-(U1-VDDA-Pad27)") (class "Default")
      (node (ref "U1") (pin "27") (pinfunction "VDDA_27") (pintype "passive"))
    )
    (net (code "136") (name "unconnected-(U1-VREF+-Pad28)") (class "Default")
      (node (ref "U1") (pin "28") (pinfunction "VREF+_28") (pintype "passive"))
    )
    (net (code "137") (name "unconnected-(U1-VREF--Pad25)") (class "Default")
      (node (ref "U1") (pin "25") (pinfunction "VREF-_25") (pintype "passive"))
    )
    (net (code "138") (name "unconnected-(U1-VSSA-Pad26)") (class "Default")
      (node (ref "U1") (pin "26") (pinfunction "VSSA_26") (pintype "passive"))
    )
    (net (code "139") (name "unconnected-(U5-ADC-Pad2)") (class "Default")
      (node (ref "U5") (pin "2") (pinfunction "ADC_2") (pintype "input"))
    )
    (net (code "140") (name "unconnected-(U5-GPIO02-Pad11)") (class "Default")
      (node (ref "U5") (pin "11") (pinfunction "GPIO02_11") (pintype "bidirectional"))
    )
    (net (code "141") (name "unconnected-(U5-GPIO04-Pad13)") (class "Default")
      (node (ref "U5") (pin "13") (pinfunction "GPIO04_13") (pintype "bidirectional"))
    )
    (net (code "142") (name "unconnected-(U5-GPIO05-Pad14)") (class "Default")
      (node (ref "U5") (pin "14") (pinfunction "GPIO05_14") (pintype "bidirectional"))
    )
    (net (code "143") (name "unconnected-(U5-GPIO12-Pad6)") (class "Default")
      (node (ref "U5") (pin "6") (pinfunction "GPIO12_6") (pintype "bidirectional"))
    )
    (net (code "144") (name "unconnected-(U5-GPIO13-Pad7)") (class "Default")
      (node (ref "U5") (pin "7") (pinfunction "GPIO13_7") (pintype "bidirectional"))
    )
    (net (code "145") (name "unconnected-(U5-GPIO14-Pad5)") (class "Default")
      (node (ref "U5") (pin "5") (pinfunction "GPIO14_5") (pintype "bidirectional"))
    )
    (net (code "146") (name "unconnected-(U5-GPIO16-Pad4)") (class "Default")
      (node (ref "U5") (pin "4") (pinfunction "GPIO16_4") (pintype "bidirectional"))
    )
    (net (code "147") (name "unconnected-(U6-BUSY-Pad6)") (class "Default")
      (node (ref "U6") (pin "6") (pinfunction "BUSY_6") (pintype "passive"))
    )
  )
)
